# 2_5VSwithcingRegulator.net
KiCad netlist of a schematic drawn in Altium Designer
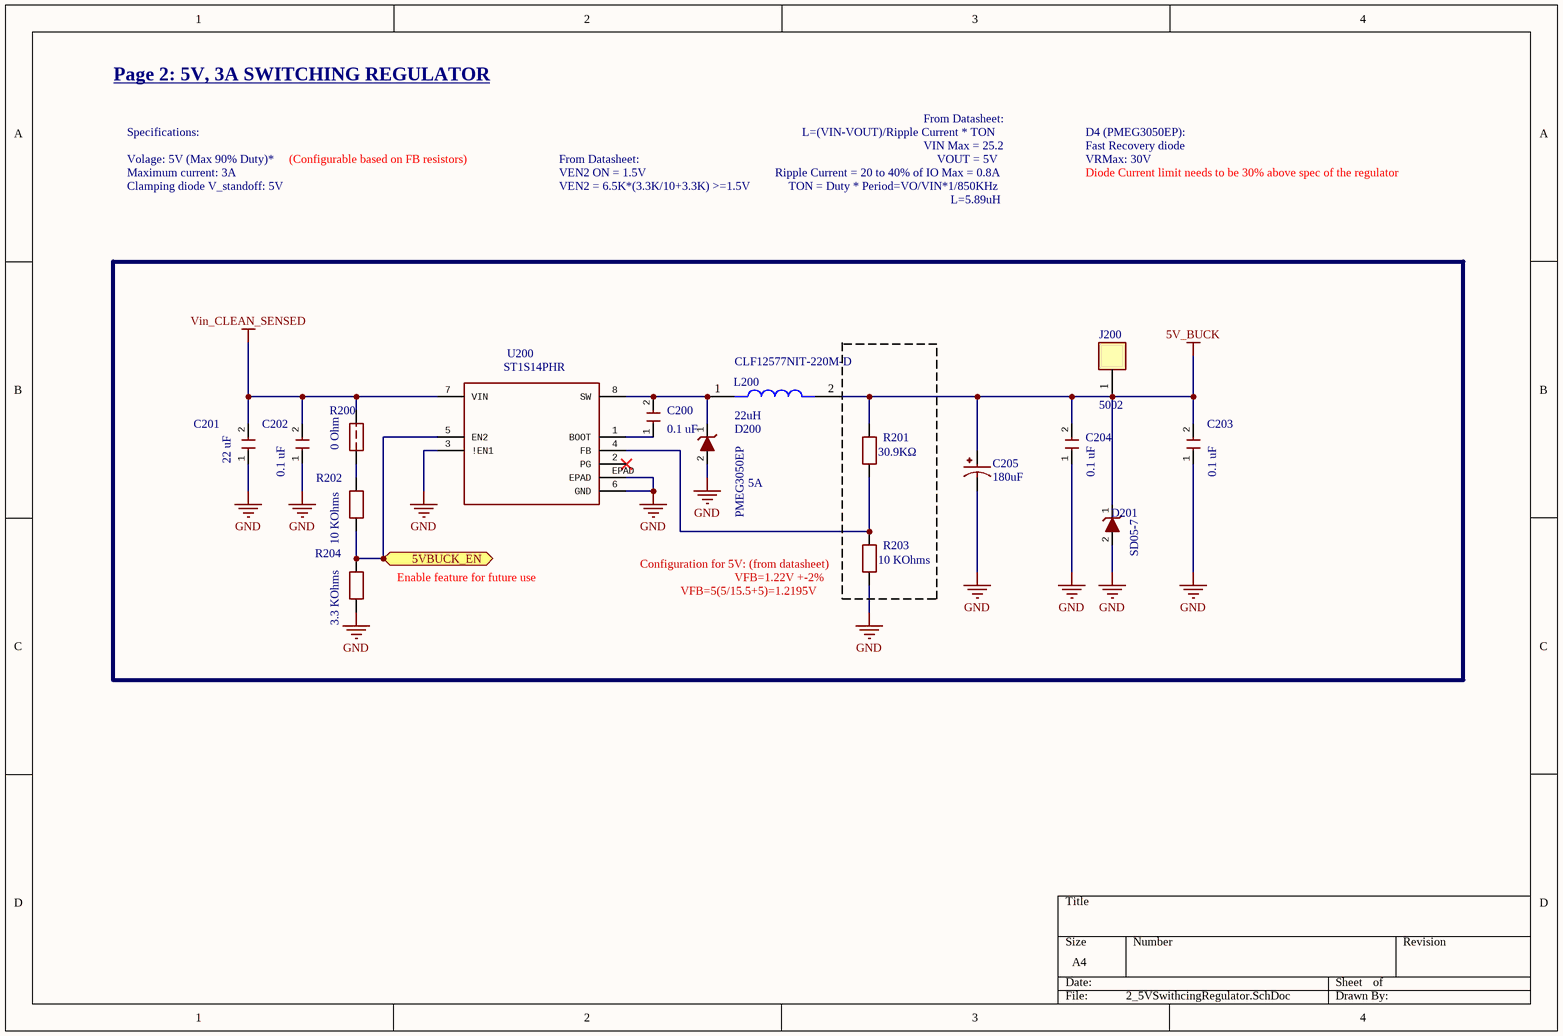
[diagram p0: 2_5VSwithcingRegulator.SchDoc]

(export (version "E")
  (design (tool "Eeschema 10.0.6"))
  (components
    (comp (ref "C200")
      (value "0.1 uF")
      (footprint "CAP_0603")
      (description "Cap Ceramic 0.1uF 50V 0603")
      (fields (field (name "PARTNUMBER") "CL10B104KB8NNNC"))
      (libsource (lib "Passives") (part "CL10B104KB8NNNC"))
    )
    (comp (ref "C201")
      (value "22 uF")
      (footprint "CAP_0603")
      (description "Cap Ceramic 22uF 10V 0603")
      (fields (field (name "PARTNUMBER") "GRM188R61A226ME15D"))
      (libsource (lib "Passives") (part "GRM188R61A226ME15D"))
    )
    (comp (ref "C202")
      (value "0.1 uF")
      (footprint "CAP_0603")
      (description "Cap Ceramic 0.1uF 50V 0603")
      (fields (field (name "PARTNUMBER") "CL10B104KB8NNNC"))
      (libsource (lib "Passives") (part "CL10B104KB8NNNC"))
    )
    (comp (ref "C203")
      (value "0.1 uF")
      (footprint "CAP_0603")
      (description "Cap Ceramic 0.1uF 50V 0603")
      (fields (field (name "PARTNUMBER") "CL10B104KB8NNNC"))
      (libsource (lib "Passives") (part "CL10B104KB8NNNC"))
    )
    (comp (ref "C204")
      (value "0.1 uF")
      (footprint "CAP_0603")
      (description "Cap Ceramic 0.1uF 50V 0603")
      (fields (field (name "PARTNUMBER") "CL10B104KB8NNNC"))
      (libsource (lib "Passives") (part "CL10B104KB8NNNC"))
    )
    (comp (ref "C205")
      (value "180uF")
      (footprint "Passives:CAP_EEEFKE181XSP")
      (description "Cap Electrolytic 180uF SMD,D6.3xL7.7mm")
      (fields (field (name "MANUFACTURER") "Panasonic") (field (name "PARTNUMBER") "EEE-FKE181XSP"))
      (libsource (lib "Passives") (part "EEEFKE181XSP"))
    )
    (comp (ref "D200")
      (value "PMEG3050EP")
      (footprint "DIODE_SOD-128")
      (description "Diode FastRecovery 30V SOD-128")
      (libsource (lib "Passives") (part "PMEG3050EP"))
    )
    (comp (ref "D201")
      (value "SD05-7")
      (footprint "DIODE_DO-214AC")
      (description "Diode TVS 5V")
      (libsource (lib "Passives") (part "SD05-7"))
    )
    (comp (ref "J200")
      (value "5002")
      (footprint "Miscellaneous:KEYSTONE_5002")
      (description "Test Point Ring Keystone")
      (fields (field (name "MANUFACTURER") "Keystone Electronics"))
      (libsource (lib "Miscellaneous") (part "5002"))
    )
    (comp (ref "L200")
      (value "CLF12577NIT-220M-D")
      (footprint "IND_TDK_CLF12577NIT")
      (description "Ind 22uH Shielded Drum Core 4.5A")
      (fields (field (name "MANUFACTURER") "TDK") (field (name "ALTIUM_VALUE") "22uH"))
      (libsource (lib "Passives") (part "CLF12577NIT-220M-D"))
    )
    (comp (ref "R200")
      (value "0 Ohm")
      (footprint "RES_0603")
      (description "Res 0Ohm 1/10W 0603")
      (fields (field (name "PARTNUMBER") "ERJ3GEY0R00V"))
      (libsource (lib "Passives") (part "ERJ3GEY0R00V"))
    )
    (comp (ref "R201")
      (value "30.9KΩ")
      (footprint "RES_0603")
      (description "Res 30.9KOhm 1/10W 0603")
      (fields (field (name "PARTNUMBER") "CRCW060330K9FKEA"))
      (libsource (lib "Passives") (part "CRCW060330K9FKEA"))
    )
    (comp (ref "R202")
      (value "10 KOhms")
      (footprint "RES_0603")
      (description "Res 10KOhms 1/10W 0603")
      (fields (field (name "PARTNUMBER") "ERJ3GEYJ103V"))
      (libsource (lib "Passives") (part "ERJ3GEYJ103V"))
    )
    (comp (ref "R203")
      (value "10 KOhms")
      (footprint "RES_0603")
      (description "Res 10KOhms 1/10W 0603")
      (fields (field (name "PARTNUMBER") "ERJ3GEYJ103V"))
      (libsource (lib "Passives") (part "ERJ3GEYJ103V"))
    )
    (comp (ref "R204")
      (value "3.3 KOhms")
      (footprint "RES_0603")
      (description "Res 3.3KOhms 1/10W 0603")
      (fields (field (name "PARTNUMBER") "ERJ-3GEYJ332V") (field (name "Comment") "P3.3KGDKR-ND"))
      (libsource (lib "Passives") (part "P3.3KGDKR-ND"))
    )
    (comp (ref "U200")
      (value "ST1S14PHR")
      (footprint "REG_SOP8_SOIC8_EPAD")
      (description "Switching Step-down In5.5V~48V Out3A")
      (libsource (lib "Regulators") (part "ST1S14PHR"))
    )
  )
  (nets
    (net (code "1") (name "/5VBUCK_EN") (class "Default")
      (node (ref "R202") (pin "1") (pinfunction "1_1") (pintype "passive"))
      (node (ref "R204") (pin "2") (pinfunction "2_2") (pintype "passive"))
      (node (ref "U200") (pin "5") (pinfunction "EN2_5") (pintype "passive"))
    )
    (net (code "2") (name "5V_BUCK") (class "Default")
      (node (ref "C203") (pin "2") (pinfunction "2_2") (pintype "passive"))
      (node (ref "C204") (pin "2") (pinfunction "2_2") (pintype "passive"))
      (node (ref "C205") (pin "1") (pinfunction "1_1") (pintype "passive"))
      (node (ref "D201") (pin "1") (pinfunction "1_1") (pintype "open_collector"))
      (node (ref "J200") (pin "1") (pintype "passive"))
      (node (ref "L200") (pin "2") (pinfunction "2_2") (pintype "passive"))
      (node (ref "R201") (pin "2") (pinfunction "2_2") (pintype "passive"))
    )
    (net (code "3") (name "GND") (class "Default")
      (node (ref "C201") (pin "1") (pinfunction "1_1") (pintype "passive"))
      (node (ref "C202") (pin "1") (pinfunction "1_1") (pintype "passive"))
      (node (ref "C203") (pin "1") (pinfunction "1_1") (pintype "passive"))
      (node (ref "C204") (pin "1") (pinfunction "1_1") (pintype "passive"))
      (node (ref "C205") (pin "2") (pinfunction "2_2") (pintype "passive"))
      (node (ref "D200") (pin "2") (pinfunction "2_2") (pintype "passive"))
      (node (ref "D201") (pin "2") (pinfunction "2_2") (pintype "open_collector"))
      (node (ref "R203") (pin "1") (pinfunction "1_1") (pintype "passive"))
      (node (ref "R204") (pin "1") (pinfunction "1_1") (pintype "passive"))
      (node (ref "U200") (pin "3") (pinfunction "!EN1_3") (pintype "passive"))
      (node (ref "U200") (pin "6") (pinfunction "GND_6") (pintype "passive"))
      (node (ref "U200") (pin "EPAD") (pinfunction "EPAD_EPAD") (pintype "passive"))
    )
    (net (code "4") (name "Net-(R200-Pad1)") (class "Default")
      (node (ref "R200") (pin "1") (pinfunction "1_1") (pintype "passive"))
      (node (ref "R202") (pin "2") (pinfunction "2_2") (pintype "passive"))
    )
    (net (code "5") (name "Net-(U200-BOOT)") (class "Default")
      (node (ref "C200") (pin "1") (pinfunction "1_1") (pintype "passive"))
      (node (ref "U200") (pin "1") (pinfunction "BOOT_1") (pintype "passive"))
    )
    (net (code "6") (name "Net-(U200-FB)") (class "Default")
      (node (ref "R201") (pin "1") (pinfunction "1_1") (pintype "passive"))
      (node (ref "R203") (pin "2") (pinfunction "2_2") (pintype "passive"))
      (node (ref "U200") (pin "4") (pinfunction "FB_4") (pintype "passive"))
    )
    (net (code "7") (name "Net-(U200-SW)") (class "Default")
      (node (ref "C200") (pin "2") (pinfunction "2_2") (pintype "passive"))
      (node (ref "D200") (pin "1") (pinfunction "1_1") (pintype "passive"))
      (node (ref "L200") (pin "1") (pinfunction "1_1") (pintype "passive"))
      (node (ref "U200") (pin "8") (pinfunction "SW_8") (pintype "passive"))
    )
    (net (code "8") (name "Vin_CLEAN_SENSED") (class "Default")
      (node (ref "C201") (pin "2") (pinfunction "2_2") (pintype "passive"))
      (node (ref "C202") (pin "2") (pinfunction "2_2") (pintype "passive"))
      (node (ref "R200") (pin "2") (pinfunction "2_2") (pintype "passive"))
      (node (ref "U200") (pin "7") (pinfunction "VIN_7") (pintype "power_in"))
    )
    (net (code "9") (name "unconnected-(U200-PG-Pad2)") (class "Default")
      (node (ref "U200") (pin "2") (pinfunction "PG_2") (pintype "passive+no_connect"))
    )
  )
)
